# BMBurner_V1_0.net
KiCad netlist of a schematic drawn in EAGLE
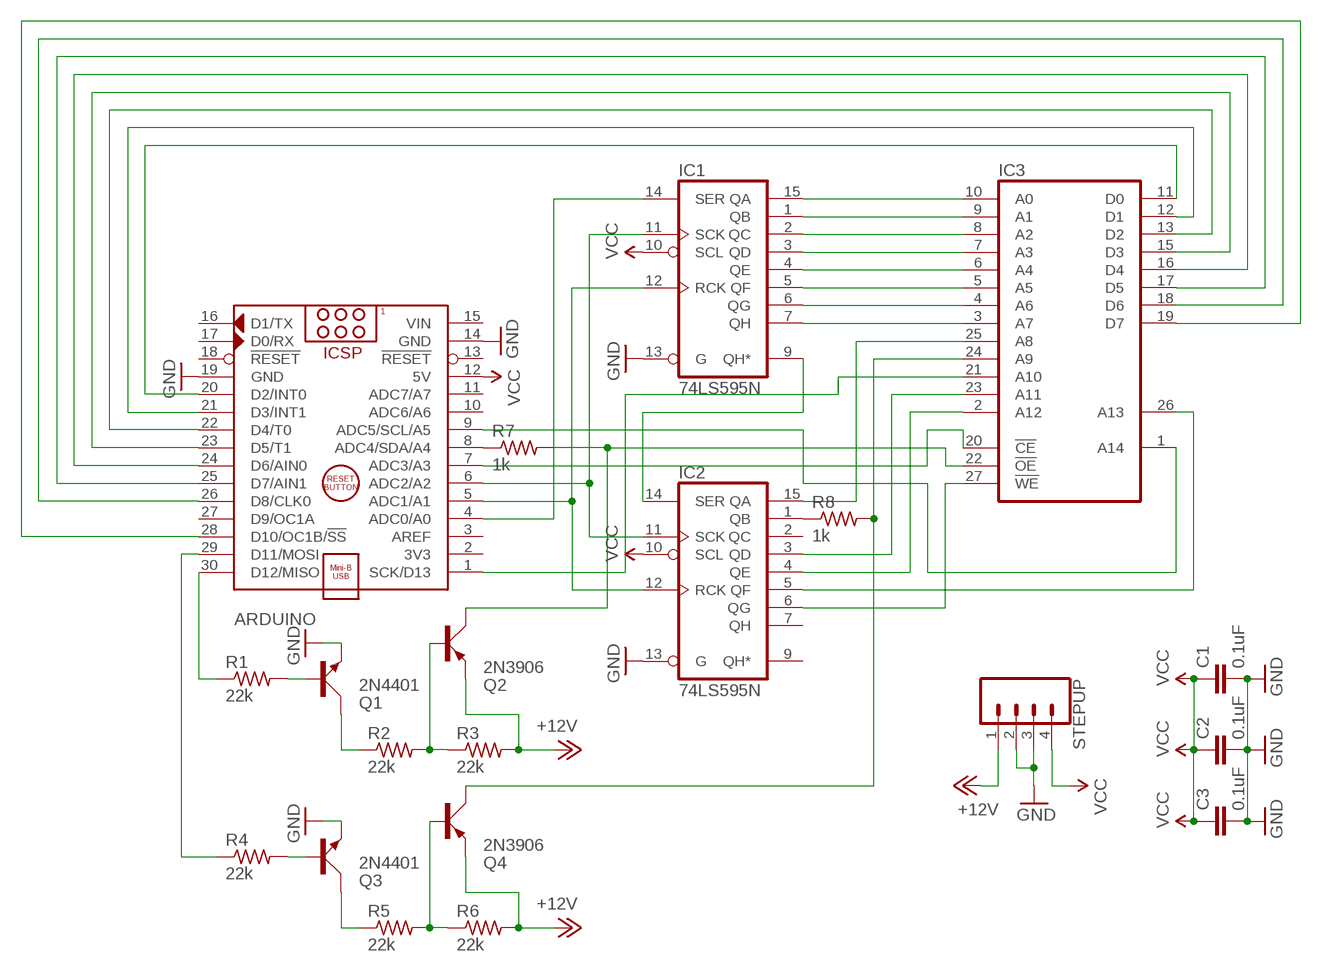
[diagram p0: schematic, sheet 1]

(export (version "E")
  (design (tool "Eeschema 10.0.6"))
  (components
    (comp (ref "ARDUINO")
      (value "ARDUINO_NANO")
      (footprint "eagle-import:ARDUINO_NANO")
      (libsource (lib "eagle-import") (part "ARDUINO_NANO"))
    )
    (comp (ref "C1")
      (value "0.1uF")
      (footprint "eagle-import:CAP-PTH-SMALL")
      (libsource (lib "eagle-import") (part "CAPPTH"))
    )
    (comp (ref "C2")
      (value "0.1uF")
      (footprint "eagle-import:CAP-PTH-SMALL")
      (libsource (lib "eagle-import") (part "CAPPTH"))
    )
    (comp (ref "C3")
      (value "0.1uF")
      (footprint "eagle-import:CAP-PTH-SMALL")
      (libsource (lib "eagle-import") (part "CAPPTH"))
    )
    (comp (ref "IC1")
      (value "74LS595N")
      (footprint "eagle-import:DIL16")
      (fields (field (name "SPICEPREFIX") "X"))
      (libsource (lib "eagle-import") (part "74595NLS"))
    )
    (comp (ref "IC2")
      (value "74LS595N")
      (footprint "eagle-import:DIL16")
      (fields (field (name "SPICEPREFIX") "X"))
      (libsource (lib "eagle-import") (part "74595NLS"))
    )
    (comp (ref "IC3")
      (value "2864")
      (footprint "eagle-import:DIL28")
      (libsource (lib "eagle-import") (part "2864"))
    )
    (comp (ref "Q1")
      (value "2N4401")
      (footprint "eagle-import:TO18A")
      (libsource (lib "eagle-import") (part "2N2222"))
    )
    (comp (ref "Q2")
      (value "2N3906")
      (footprint "eagle-import:TO92D")
      (libsource (lib "eagle-import") (part "2N3906"))
    )
    (comp (ref "Q3")
      (value "2N4401")
      (footprint "eagle-import:TO18A")
      (libsource (lib "eagle-import") (part "2N2222"))
    )
    (comp (ref "Q4")
      (value "2N3906")
      (footprint "eagle-import:TO92D")
      (libsource (lib "eagle-import") (part "2N3906"))
    )
    (comp (ref "R1")
      (value "22k")
      (footprint "eagle-import:0207_10")
      (fields (field (name "SPICEPREFIX") "R"))
      (libsource (lib "eagle-import") (part "R-US_0207/10"))
    )
    (comp (ref "R2")
      (value "22k")
      (footprint "eagle-import:0207_10")
      (libsource (lib "eagle-import") (part "R-US_0207/10"))
    )
    (comp (ref "R3")
      (value "22k")
      (footprint "eagle-import:0207_10")
      (libsource (lib "eagle-import") (part "R-US_0207/10"))
    )
    (comp (ref "R4")
      (value "22k")
      (footprint "eagle-import:0207_10")
      (libsource (lib "eagle-import") (part "R-US_0207/10"))
    )
    (comp (ref "R5")
      (value "22k")
      (footprint "eagle-import:0207_10")
      (libsource (lib "eagle-import") (part "R-US_0207/10"))
    )
    (comp (ref "R6")
      (value "22k")
      (footprint "eagle-import:0207_10")
      (libsource (lib "eagle-import") (part "R-US_0207/10"))
    )
    (comp (ref "R7")
      (value "1k")
      (footprint "eagle-import:0207_10")
      (libsource (lib "eagle-import") (part "R-US_0207/10"))
    )
    (comp (ref "R8")
      (value "1k")
      (footprint "eagle-import:0207_10")
      (libsource (lib "eagle-import") (part "R-US_0207/10"))
    )
    (comp (ref "STEPUP")
      (value "CONN_04")
      (footprint "eagle-import:1X04")
      (libsource (lib "eagle-import") (part "CONN_04"))
    )
  )
  (nets
    (net (code "1") (name "+12V") (class "Default")
      (node (ref "Q2") (pin "E") (pinfunction "E_E") (pintype "passive"))
      (node (ref "Q4") (pin "E") (pinfunction "E_E") (pintype "passive"))
      (node (ref "R3") (pin "2") (pinfunction "2_2") (pintype "passive"))
      (node (ref "R6") (pin "2") (pinfunction "2_2") (pintype "passive"))
      (node (ref "STEPUP") (pin "1") (pinfunction "1_1") (pintype "passive"))
    )
    (net (code "2") (name "/VIN") (class "Default")
      (node (ref "ARDUINO") (pin "15") (pinfunction "VIN_15") (pintype "power_in"))
    )
    (net (code "3") (name "GND") (class "Default")
      (node (ref "ARDUINO") (pin "14") (pinfunction "GND_14") (pintype "power_in"))
      (node (ref "ARDUINO") (pin "19") (pinfunction "GND_19") (pintype "power_in"))
      (node (ref "C1") (pin "2") (pinfunction "2_2") (pintype "passive"))
      (node (ref "C2") (pin "2") (pinfunction "2_2") (pintype "passive"))
      (node (ref "C3") (pin "2") (pinfunction "2_2") (pintype "passive"))
      (node (ref "IC1") (pin "13") (pinfunction "G_13") (pintype "input"))
      (node (ref "IC2") (pin "13") (pinfunction "G_13") (pintype "input"))
      (node (ref "Q1") (pin "E") (pinfunction "E_E") (pintype "passive"))
      (node (ref "Q3") (pin "E") (pinfunction "E_E") (pintype "passive"))
      (node (ref "STEPUP") (pin "2") (pinfunction "2_2") (pintype "passive"))
      (node (ref "STEPUP") (pin "3") (pinfunction "3_3") (pintype "passive"))
    )
    (net (code "4") (name "Net-(ARDUINO-ADC0{slash}A0)") (class "Default")
      (node (ref "ARDUINO") (pin "4") (pinfunction "ADC0/A0_4") (pintype "bidirectional"))
      (node (ref "IC1") (pin "14") (pinfunction "SER_14") (pintype "input"))
    )
    (net (code "5") (name "Net-(ARDUINO-ADC1{slash}A1)") (class "Default")
      (node (ref "ARDUINO") (pin "5") (pinfunction "ADC1/A1_5") (pintype "bidirectional"))
      (node (ref "IC1") (pin "12") (pinfunction "RCK_12") (pintype "input"))
      (node (ref "IC2") (pin "12") (pinfunction "RCK_12") (pintype "input"))
    )
    (net (code "6") (name "Net-(ARDUINO-ADC2{slash}A2)") (class "Default")
      (node (ref "ARDUINO") (pin "6") (pinfunction "ADC2/A2_6") (pintype "bidirectional"))
      (node (ref "IC1") (pin "11") (pinfunction "SCK_11") (pintype "input"))
      (node (ref "IC2") (pin "11") (pinfunction "SCK_11") (pintype "input"))
    )
    (net (code "7") (name "Net-(ARDUINO-ADC3{slash}A3)") (class "Default")
      (node (ref "ARDUINO") (pin "7") (pinfunction "ADC3/A3_7") (pintype "bidirectional"))
      (node (ref "IC3") (pin "20") (pinfunction "~{CE}_20") (pintype "input"))
    )
    (net (code "8") (name "Net-(ARDUINO-ADC4{slash}SDA{slash}A4)") (class "Default")
      (node (ref "ARDUINO") (pin "8") (pinfunction "ADC4/SDA/A4_8") (pintype "bidirectional"))
      (node (ref "R7") (pin "1") (pinfunction "1_1") (pintype "passive"))
    )
    (net (code "9") (name "Net-(ARDUINO-ADC5{slash}SCL{slash}A5)") (class "Default")
      (node (ref "ARDUINO") (pin "9") (pinfunction "ADC5/SCL/A5_9") (pintype "bidirectional"))
      (node (ref "IC3") (pin "1") (pinfunction "A14_1") (pintype "input"))
    )
    (net (code "10") (name "Net-(ARDUINO-D2{slash}INT0)") (class "Default")
      (node (ref "ARDUINO") (pin "20") (pinfunction "D2/INT0_20") (pintype "bidirectional"))
      (node (ref "IC3") (pin "11") (pinfunction "D0_11") (pintype "bidirectional"))
    )
    (net (code "11") (name "Net-(ARDUINO-D3{slash}INT1)") (class "Default")
      (node (ref "ARDUINO") (pin "21") (pinfunction "D3/INT1_21") (pintype "bidirectional"))
      (node (ref "IC3") (pin "12") (pinfunction "D1_12") (pintype "bidirectional"))
    )
    (net (code "12") (name "Net-(ARDUINO-D4{slash}T0)") (class "Default")
      (node (ref "ARDUINO") (pin "22") (pinfunction "D4/T0_22") (pintype "bidirectional"))
      (node (ref "IC3") (pin "13") (pinfunction "D2_13") (pintype "bidirectional"))
    )
    (net (code "13") (name "Net-(ARDUINO-D5{slash}T1)") (class "Default")
      (node (ref "ARDUINO") (pin "23") (pinfunction "D5/T1_23") (pintype "bidirectional"))
      (node (ref "IC3") (pin "15") (pinfunction "D3_15") (pintype "bidirectional"))
    )
    (net (code "14") (name "Net-(ARDUINO-D6{slash}AIN0)") (class "Default")
      (node (ref "ARDUINO") (pin "24") (pinfunction "D6/AIN0_24") (pintype "bidirectional"))
      (node (ref "IC3") (pin "16") (pinfunction "D4_16") (pintype "bidirectional"))
    )
    (net (code "15") (name "Net-(ARDUINO-D7{slash}AIN1)") (class "Default")
      (node (ref "ARDUINO") (pin "25") (pinfunction "D7/AIN1_25") (pintype "bidirectional"))
      (node (ref "IC3") (pin "17") (pinfunction "D5_17") (pintype "bidirectional"))
    )
    (net (code "16") (name "Net-(ARDUINO-D8{slash}CLK0)") (class "Default")
      (node (ref "ARDUINO") (pin "26") (pinfunction "D8/CLK0_26") (pintype "bidirectional"))
      (node (ref "IC3") (pin "18") (pinfunction "D6_18") (pintype "bidirectional"))
    )
    (net (code "17") (name "Net-(ARDUINO-D10{slash}OC1B{slash}~{SS})") (class "Default")
      (node (ref "ARDUINO") (pin "28") (pinfunction "D10/OC1B/~{SS}_28") (pintype "bidirectional"))
      (node (ref "IC3") (pin "19") (pinfunction "D7_19") (pintype "bidirectional"))
    )
    (net (code "18") (name "Net-(ARDUINO-D11{slash}MOSI)") (class "Default")
      (node (ref "ARDUINO") (pin "29") (pinfunction "D11/MOSI_29") (pintype "bidirectional"))
      (node (ref "R4") (pin "1") (pinfunction "1_1") (pintype "passive"))
    )
    (net (code "19") (name "Net-(ARDUINO-D12{slash}MISO)") (class "Default")
      (node (ref "ARDUINO") (pin "30") (pinfunction "D12/MISO_30") (pintype "bidirectional"))
      (node (ref "R1") (pin "1") (pinfunction "1_1") (pintype "passive"))
    )
    (net (code "20") (name "Net-(ARDUINO-SCK{slash}D13)") (class "Default")
      (node (ref "ARDUINO") (pin "1") (pinfunction "SCK/D13_1") (pintype "bidirectional"))
      (node (ref "IC3") (pin "21") (pinfunction "A10_21") (pintype "input"))
    )
    (net (code "21") (name "Net-(IC1A-QA)") (class "Default")
      (node (ref "IC1") (pin "15") (pinfunction "QA_15") (pintype "tri_state"))
      (node (ref "IC3") (pin "10") (pinfunction "A0_10") (pintype "input"))
    )
    (net (code "22") (name "Net-(IC1A-QB)") (class "Default")
      (node (ref "IC1") (pin "1") (pinfunction "QB_1") (pintype "tri_state"))
      (node (ref "IC3") (pin "9") (pinfunction "A1_9") (pintype "input"))
    )
    (net (code "23") (name "Net-(IC1A-QC)") (class "Default")
      (node (ref "IC1") (pin "2") (pinfunction "QC_2") (pintype "tri_state"))
      (node (ref "IC3") (pin "8") (pinfunction "A2_8") (pintype "input"))
    )
    (net (code "24") (name "Net-(IC1A-QD)") (class "Default")
      (node (ref "IC1") (pin "3") (pinfunction "QD_3") (pintype "tri_state"))
      (node (ref "IC3") (pin "7") (pinfunction "A3_7") (pintype "input"))
    )
    (net (code "25") (name "Net-(IC1A-QE)") (class "Default")
      (node (ref "IC1") (pin "4") (pinfunction "QE_4") (pintype "tri_state"))
      (node (ref "IC3") (pin "6") (pinfunction "A4_6") (pintype "input"))
    )
    (net (code "26") (name "Net-(IC1A-QF)") (class "Default")
      (node (ref "IC1") (pin "5") (pinfunction "QF_5") (pintype "tri_state"))
      (node (ref "IC3") (pin "5") (pinfunction "A5_5") (pintype "input"))
    )
    (net (code "27") (name "Net-(IC1A-QG)") (class "Default")
      (node (ref "IC1") (pin "6") (pinfunction "QG_6") (pintype "tri_state"))
      (node (ref "IC3") (pin "4") (pinfunction "A6_4") (pintype "input"))
    )
    (net (code "28") (name "Net-(IC1A-QH)") (class "Default")
      (node (ref "IC1") (pin "7") (pinfunction "QH_7") (pintype "tri_state"))
      (node (ref "IC3") (pin "3") (pinfunction "A7_3") (pintype "input"))
    )
    (net (code "29") (name "Net-(IC1A-QH*)") (class "Default")
      (node (ref "IC1") (pin "9") (pinfunction "QH*_9") (pintype "tri_state"))
      (node (ref "IC2") (pin "14") (pinfunction "SER_14") (pintype "input"))
    )
    (net (code "30") (name "Net-(IC2A-QA)") (class "Default")
      (node (ref "IC2") (pin "15") (pinfunction "QA_15") (pintype "tri_state"))
      (node (ref "IC3") (pin "25") (pinfunction "A8_25") (pintype "input"))
    )
    (net (code "31") (name "Net-(IC2A-QB)") (class "Default")
      (node (ref "IC2") (pin "1") (pinfunction "QB_1") (pintype "tri_state"))
      (node (ref "R8") (pin "1") (pinfunction "1_1") (pintype "passive"))
    )
    (net (code "32") (name "Net-(IC2A-QD)") (class "Default")
      (node (ref "IC2") (pin "3") (pinfunction "QD_3") (pintype "tri_state"))
      (node (ref "IC3") (pin "23") (pinfunction "A11_23") (pintype "input"))
    )
    (net (code "33") (name "Net-(IC2A-QE)") (class "Default")
      (node (ref "IC2") (pin "4") (pinfunction "QE_4") (pintype "tri_state"))
      (node (ref "IC3") (pin "2") (pinfunction "A12_2") (pintype "input"))
    )
    (net (code "34") (name "Net-(IC2A-QF)") (class "Default")
      (node (ref "IC2") (pin "5") (pinfunction "QF_5") (pintype "tri_state"))
      (node (ref "IC3") (pin "26") (pinfunction "A13_26") (pintype "input"))
    )
    (net (code "35") (name "Net-(IC2A-QG)") (class "Default")
      (node (ref "IC2") (pin "6") (pinfunction "QG_6") (pintype "tri_state"))
      (node (ref "IC3") (pin "27") (pinfunction "~{WE}_27") (pintype "input"))
    )
    (net (code "36") (name "Net-(IC3A-A9)") (class "Default")
      (node (ref "IC3") (pin "24") (pinfunction "A9_24") (pintype "input"))
      (node (ref "Q4") (pin "C") (pinfunction "C_C") (pintype "passive"))
      (node (ref "R8") (pin "2") (pinfunction "2_2") (pintype "passive"))
    )
    (net (code "37") (name "Net-(IC3A-~{OE})") (class "Default")
      (node (ref "IC3") (pin "22") (pinfunction "~{OE}_22") (pintype "input"))
      (node (ref "Q2") (pin "C") (pinfunction "C_C") (pintype "passive"))
      (node (ref "R7") (pin "2") (pinfunction "2_2") (pintype "passive"))
    )
    (net (code "38") (name "Net-(Q1-PadB)") (class "Default")
      (node (ref "Q1") (pin "B") (pinfunction "B_B") (pintype "passive"))
      (node (ref "R1") (pin "2") (pinfunction "2_2") (pintype "passive"))
    )
    (net (code "39") (name "Net-(Q1-PadC)") (class "Default")
      (node (ref "Q1") (pin "C") (pinfunction "C_C") (pintype "passive"))
      (node (ref "R2") (pin "1") (pinfunction "1_1") (pintype "passive"))
    )
    (net (code "40") (name "Net-(Q2-PadB)") (class "Default")
      (node (ref "Q2") (pin "B") (pinfunction "B_B") (pintype "passive"))
      (node (ref "R2") (pin "2") (pinfunction "2_2") (pintype "passive"))
      (node (ref "R3") (pin "1") (pinfunction "1_1") (pintype "passive"))
    )
    (net (code "41") (name "Net-(Q3-PadB)") (class "Default")
      (node (ref "Q3") (pin "B") (pinfunction "B_B") (pintype "passive"))
      (node (ref "R4") (pin "2") (pinfunction "2_2") (pintype "passive"))
    )
    (net (code "42") (name "Net-(Q3-PadC)") (class "Default")
      (node (ref "Q3") (pin "C") (pinfunction "C_C") (pintype "passive"))
      (node (ref "R5") (pin "1") (pinfunction "1_1") (pintype "passive"))
    )
    (net (code "43") (name "Net-(Q4-PadB)") (class "Default")
      (node (ref "Q4") (pin "B") (pinfunction "B_B") (pintype "passive"))
      (node (ref "R5") (pin "2") (pinfunction "2_2") (pintype "passive"))
      (node (ref "R6") (pin "1") (pinfunction "1_1") (pintype "passive"))
    )
    (net (code "44") (name "VCC") (class "Default")
      (node (ref "ARDUINO") (pin "12") (pinfunction "5V_12") (pintype "power_in"))
      (node (ref "C1") (pin "1") (pinfunction "1_1") (pintype "passive"))
      (node (ref "C2") (pin "1") (pinfunction "1_1") (pintype "passive"))
      (node (ref "C3") (pin "1") (pinfunction "1_1") (pintype "passive"))
      (node (ref "IC1") (pin "10") (pinfunction "SCL_10") (pintype "input"))
      (node (ref "IC2") (pin "10") (pinfunction "SCL_10") (pintype "input"))
      (node (ref "STEPUP") (pin "4") (pinfunction "4_4") (pintype "passive"))
    )
    (net (code "45") (name "unconnected-(ARDUINO-3V3-Pad2)") (class "Default")
      (node (ref "ARDUINO") (pin "2") (pinfunction "3V3_2") (pintype "output"))
    )
    (net (code "46") (name "unconnected-(ARDUINO-ADC6{slash}A6-Pad10)") (class "Default")
      (node (ref "ARDUINO") (pin "10") (pinfunction "ADC6/A6_10") (pintype "bidirectional"))
    )
    (net (code "47") (name "unconnected-(ARDUINO-ADC7{slash}A7-Pad11)") (class "Default")
      (node (ref "ARDUINO") (pin "11") (pinfunction "ADC7/A7_11") (pintype "bidirectional"))
    )
    (net (code "48") (name "unconnected-(ARDUINO-AREF-Pad3)") (class "Default")
      (node (ref "ARDUINO") (pin "3") (pinfunction "AREF_3") (pintype "input"))
    )
    (net (code "49") (name "unconnected-(ARDUINO-D0{slash}RX-Pad17)") (class "Default")
      (node (ref "ARDUINO") (pin "17") (pinfunction "D0/RX_17") (pintype "bidirectional"))
    )
    (net (code "50") (name "unconnected-(ARDUINO-D1{slash}TX-Pad16)") (class "Default")
      (node (ref "ARDUINO") (pin "16") (pinfunction "D1/TX_16") (pintype "bidirectional"))
    )
    (net (code "51") (name "unconnected-(ARDUINO-D9{slash}OC1A-Pad27)") (class "Default")
      (node (ref "ARDUINO") (pin "27") (pinfunction "D9/OC1A_27") (pintype "bidirectional"))
    )
    (net (code "52") (name "unconnected-(ARDUINO-~{RESET}-Pad13)") (class "Default")
      (node (ref "ARDUINO") (pin "13") (pinfunction "~{RESET}_13") (pintype "input"))
    )
    (net (code "53") (name "unconnected-(ARDUINO-~{RESET}-Pad18)") (class "Default")
      (node (ref "ARDUINO") (pin "18") (pinfunction "~{RESET}_18") (pintype "input"))
    )
    (net (code "54") (name "unconnected-(IC2A-QC-Pad2)") (class "Default")
      (node (ref "IC2") (pin "2") (pinfunction "QC_2") (pintype "tri_state"))
    )
    (net (code "55") (name "unconnected-(IC2A-QH*-Pad9)") (class "Default")
      (node (ref "IC2") (pin "9") (pinfunction "QH*_9") (pintype "tri_state"))
    )
    (net (code "56") (name "unconnected-(IC2A-QH-Pad7)") (class "Default")
      (node (ref "IC2") (pin "7") (pinfunction "QH_7") (pintype "tri_state"))
    )
  )
)
